# SunriseClockSwitchesv2.net
KiCad netlist of a schematic drawn in EAGLE
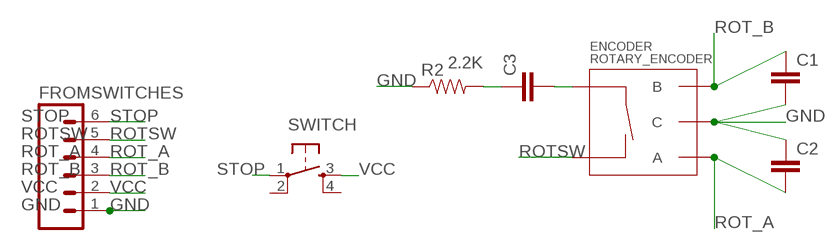
[diagram p0: schematic, sheet 1]

(export (version "E")
  (design (tool "Eeschema 10.0.6"))
  (components
    (comp (ref "C1")
      (value "CAPEZ")
      (footprint "eagle-import:CAP-PTH-SMALLEZ")
      (libsource (lib "eagle-import") (part "CAPEZ"))
    )
    (comp (ref "C2")
      (value "CAPEZ")
      (footprint "eagle-import:CAP-PTH-SMALLEZ")
      (libsource (lib "eagle-import") (part "CAPEZ"))
    )
    (comp (ref "C3")
      (value "CAPEZ")
      (footprint "eagle-import:CAP-PTH-SMALLEZ")
      (libsource (lib "eagle-import") (part "CAPEZ"))
    )
    (comp (ref "ENCODER")
      (value "ROTARY_ENCODER")
      (footprint "eagle-import:ROTARY_ENC_PLAIN")
      (libsource (lib "eagle-import") (part "ROTARTY_ENCODER"))
    )
    (comp (ref "FROMSWITCHES")
      (value "M06LOCK")
      (footprint "eagle-import:1X06_LOCK")
      (libsource (lib "eagle-import") (part "M06LOCK"))
    )
    (comp (ref "R2")
      (value "RESISTORPTH-1/4W")
      (footprint "eagle-import:AXIAL-0.4")
      (fields (field (name "R2") "2.2K"))
      (libsource (lib "eagle-import") (part "RESISTORPTH-1/4W"))
    )
    (comp (ref "SWITCH")
      (value "TAC_SWITCHPTH")
      (footprint "eagle-import:TACTILE-PTH")
      (libsource (lib "eagle-import") (part "TAC_SWITCHPTH"))
    )
  )
  (nets
    (net (code "1") (name "/GND") (class "Default")
      (node (ref "C1") (pin "2") (pinfunction "2_2") (pintype "passive"))
      (node (ref "C2") (pin "1") (pinfunction "1_1") (pintype "passive"))
      (node (ref "ENCODER") (pin "C") (pinfunction "C_C") (pintype "bidirectional"))
      (node (ref "FROMSWITCHES") (pin "1") (pinfunction "1_1") (pintype "passive"))
      (node (ref "R2") (pin "P$1") (pinfunction "1_P$1") (pintype "passive"))
    )
    (net (code "2") (name "/ROTSW") (class "Default")
      (node (ref "ENCODER") (pin "SW-") (pinfunction "SW-_SW-") (pintype "bidirectional"))
      (node (ref "FROMSWITCHES") (pin "5") (pinfunction "5_5") (pintype "passive"))
    )
    (net (code "3") (name "/ROT_A") (class "Default")
      (node (ref "C2") (pin "2") (pinfunction "2_2") (pintype "passive"))
      (node (ref "ENCODER") (pin "A") (pinfunction "A_A") (pintype "bidirectional"))
      (node (ref "FROMSWITCHES") (pin "4") (pinfunction "4_4") (pintype "passive"))
    )
    (net (code "4") (name "/ROT_B") (class "Default")
      (node (ref "C1") (pin "1") (pinfunction "1_1") (pintype "passive"))
      (node (ref "ENCODER") (pin "B") (pinfunction "B_B") (pintype "bidirectional"))
      (node (ref "FROMSWITCHES") (pin "3") (pinfunction "3_3") (pintype "passive"))
    )
    (net (code "5") (name "/STOP") (class "Default")
      (node (ref "FROMSWITCHES") (pin "6") (pinfunction "6_6") (pintype "passive"))
      (node (ref "SWITCH") (pin "1") (pinfunction "1_1") (pintype "passive"))
    )
    (net (code "6") (name "/VCC") (class "Default")
      (node (ref "FROMSWITCHES") (pin "2") (pinfunction "2_2") (pintype "passive"))
      (node (ref "SWITCH") (pin "3") (pinfunction "3_3") (pintype "passive"))
    )
    (net (code "7") (name "Net-(C3-Pad2)") (class "Default")
      (node (ref "C3") (pin "2") (pinfunction "2_2") (pintype "passive"))
      (node (ref "ENCODER") (pin "SW+") (pinfunction "SW+_SW+") (pintype "bidirectional"))
    )
    (net (code "8") (name "Net-(R2-2)") (class "Default")
      (node (ref "C3") (pin "1") (pinfunction "1_1") (pintype "passive"))
      (node (ref "R2") (pin "P$2") (pinfunction "2_P$2") (pintype "passive"))
    )
    (net (code "9") (name "unconnected-(SWITCH-Pad2)") (class "Default")
      (node (ref "SWITCH") (pin "2") (pinfunction "2_2") (pintype "passive"))
    )
    (net (code "10") (name "unconnected-(SWITCH-Pad4)") (class "Default")
      (node (ref "SWITCH") (pin "4") (pinfunction "4_4") (pintype "passive"))
    )
  )
)
